# adapter.net
KiCad netlist of a schematic drawn in EAGLE
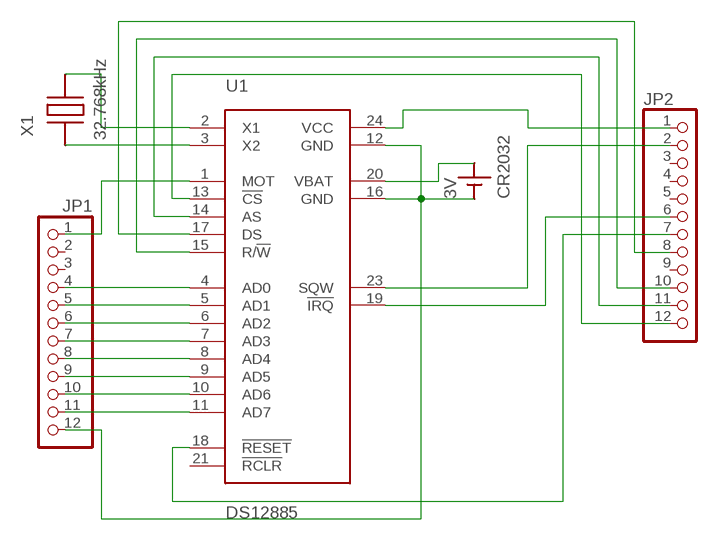
[diagram p0: schematic, sheet 1]

(export (version "E")
  (design (tool "Eeschema 10.0.6"))
  (components
    (comp (ref "3V")
      (value "CR2032")
      (footprint "eagle-import:CR2032H")
      (libsource (lib "eagle-import") (part "CR2032"))
    )
    (comp (ref "JP1")
      (value "PINHD-1X12")
      (footprint "eagle-import:1X12")
      (libsource (lib "eagle-import") (part "PINHD-1X12"))
    )
    (comp (ref "JP2")
      (value "PINHD-1X12")
      (footprint "eagle-import:1X12")
      (libsource (lib "eagle-import") (part "PINHD-1X12"))
    )
    (comp (ref "U1")
      (value "DS12885")
      (footprint "eagle-import:DIP24")
      (libsource (lib "eagle-import") (part "DS12885"))
    )
    (comp (ref "X1")
      (value "32.768kHz")
      (footprint "eagle-import:2PAD")
      (libsource (lib "eagle-import") (part "CRYSTAL"))
    )
  )
  (nets
    (net (code "1") (name "Net-(3V-GND)") (class "Default")
      (node (ref "3V") (pin "-") (pinfunction "GND_-") (pintype "power_in"))
      (node (ref "JP1") (pin "12") (pinfunction "12_12") (pintype "passive"))
      (node (ref "U1") (pin "12") (pinfunction "GND_12") (pintype "power_in"))
      (node (ref "U1") (pin "16") (pinfunction "GND_16") (pintype "power_in"))
    )
    (net (code "2") (name "Net-(3V-VCC)") (class "Default")
      (node (ref "3V") (pin "+") (pinfunction "VCC_+") (pintype "power_in"))
      (node (ref "U1") (pin "20") (pinfunction "VBAT_20") (pintype "power_in"))
    )
    (net (code "3") (name "Net-(U1-AD0)") (class "Default")
      (node (ref "JP1") (pin "4") (pinfunction "4_4") (pintype "passive"))
      (node (ref "U1") (pin "4") (pinfunction "AD0_4") (pintype "bidirectional"))
    )
    (net (code "4") (name "Net-(U1-AD1)") (class "Default")
      (node (ref "JP1") (pin "5") (pinfunction "5_5") (pintype "passive"))
      (node (ref "U1") (pin "5") (pinfunction "AD1_5") (pintype "bidirectional"))
    )
    (net (code "5") (name "Net-(U1-AD2)") (class "Default")
      (node (ref "JP1") (pin "6") (pinfunction "6_6") (pintype "passive"))
      (node (ref "U1") (pin "6") (pinfunction "AD2_6") (pintype "bidirectional"))
    )
    (net (code "6") (name "Net-(U1-AD3)") (class "Default")
      (node (ref "JP1") (pin "7") (pinfunction "7_7") (pintype "passive"))
      (node (ref "U1") (pin "7") (pinfunction "AD3_7") (pintype "bidirectional"))
    )
    (net (code "7") (name "Net-(U1-AD4)") (class "Default")
      (node (ref "JP1") (pin "8") (pinfunction "8_8") (pintype "passive"))
      (node (ref "U1") (pin "8") (pinfunction "AD4_8") (pintype "bidirectional"))
    )
    (net (code "8") (name "Net-(U1-AD5)") (class "Default")
      (node (ref "JP1") (pin "9") (pinfunction "9_9") (pintype "passive"))
      (node (ref "U1") (pin "9") (pinfunction "AD5_9") (pintype "bidirectional"))
    )
    (net (code "9") (name "Net-(U1-AD6)") (class "Default")
      (node (ref "JP1") (pin "10") (pinfunction "10_10") (pintype "passive"))
      (node (ref "U1") (pin "10") (pinfunction "AD6_10") (pintype "bidirectional"))
    )
    (net (code "10") (name "Net-(U1-AD7)") (class "Default")
      (node (ref "JP1") (pin "11") (pinfunction "11_11") (pintype "passive"))
      (node (ref "U1") (pin "11") (pinfunction "AD7_11") (pintype "bidirectional"))
    )
    (net (code "11") (name "Net-(U1-AS)") (class "Default")
      (node (ref "JP2") (pin "11") (pinfunction "11_11") (pintype "passive"))
      (node (ref "U1") (pin "14") (pinfunction "AS_14") (pintype "input"))
    )
    (net (code "12") (name "Net-(U1-DS)") (class "Default")
      (node (ref "JP2") (pin "8") (pinfunction "8_8") (pintype "passive"))
      (node (ref "U1") (pin "17") (pinfunction "DS_17") (pintype "input"))
    )
    (net (code "13") (name "Net-(U1-MOT)") (class "Default")
      (node (ref "JP1") (pin "1") (pinfunction "1_1") (pintype "passive"))
      (node (ref "U1") (pin "1") (pinfunction "MOT_1") (pintype "input"))
    )
    (net (code "14") (name "Net-(U1-R{slash}~{W})") (class "Default")
      (node (ref "JP2") (pin "10") (pinfunction "10_10") (pintype "passive"))
      (node (ref "U1") (pin "15") (pinfunction "R/~{W}_15") (pintype "input"))
    )
    (net (code "15") (name "Net-(U1-SQW)") (class "Default")
      (node (ref "JP2") (pin "2") (pinfunction "2_2") (pintype "passive"))
      (node (ref "U1") (pin "23") (pinfunction "SQW_23") (pintype "output"))
    )
    (net (code "16") (name "Net-(U1-VCC)") (class "Default")
      (node (ref "JP2") (pin "1") (pinfunction "1_1") (pintype "passive"))
      (node (ref "U1") (pin "24") (pinfunction "VCC_24") (pintype "power_in"))
    )
    (net (code "17") (name "Net-(U1-X1)") (class "Default")
      (node (ref "U1") (pin "2") (pinfunction "X1_2") (pintype "input"))
      (node (ref "X1") (pin "1") (pinfunction "X2_1") (pintype "bidirectional"))
    )
    (net (code "18") (name "Net-(U1-X2)") (class "Default")
      (node (ref "U1") (pin "3") (pinfunction "X2_3") (pintype "output"))
      (node (ref "X1") (pin "2") (pinfunction "X1_2") (pintype "bidirectional"))
    )
    (net (code "19") (name "Net-(U1-~{CS})") (class "Default")
      (node (ref "JP2") (pin "12") (pinfunction "12_12") (pintype "passive"))
      (node (ref "U1") (pin "13") (pinfunction "~{CS}_13") (pintype "input"))
    )
    (net (code "20") (name "Net-(U1-~{IRQ})") (class "Default")
      (node (ref "JP2") (pin "6") (pinfunction "6_6") (pintype "passive"))
      (node (ref "U1") (pin "19") (pinfunction "~{IRQ}_19") (pintype "output"))
    )
    (net (code "21") (name "Net-(U1-~{RESET})") (class "Default")
      (node (ref "JP2") (pin "7") (pinfunction "7_7") (pintype "passive"))
      (node (ref "U1") (pin "18") (pinfunction "~{RESET}_18") (pintype "input"))
    )
    (net (code "22") (name "unconnected-(JP1-Pad2)") (class "Default")
      (node (ref "JP1") (pin "2") (pinfunction "2_2") (pintype "passive"))
    )
    (net (code "23") (name "unconnected-(JP1-Pad3)") (class "Default")
      (node (ref "JP1") (pin "3") (pinfunction "3_3") (pintype "passive"))
    )
    (net (code "24") (name "unconnected-(JP2-Pad3)") (class "Default")
      (node (ref "JP2") (pin "3") (pinfunction "3_3") (pintype "passive"))
    )
    (net (code "25") (name "unconnected-(JP2-Pad4)") (class "Default")
      (node (ref "JP2") (pin "4") (pinfunction "4_4") (pintype "passive"))
    )
    (net (code "26") (name "unconnected-(JP2-Pad5)") (class "Default")
      (node (ref "JP2") (pin "5") (pinfunction "5_5") (pintype "passive"))
    )
    (net (code "27") (name "unconnected-(JP2-Pad9)") (class "Default")
      (node (ref "JP2") (pin "9") (pinfunction "9_9") (pintype "passive"))
    )
    (net (code "28") (name "unconnected-(U1-~{RCLR}-Pad21)") (class "Default")
      (node (ref "U1") (pin "21") (pinfunction "~{RCLR}_21") (pintype "input"))
    )
  )
)
